# WikiTFT-2_8.net
KiCad netlist of a schematic drawn in Altium Designer
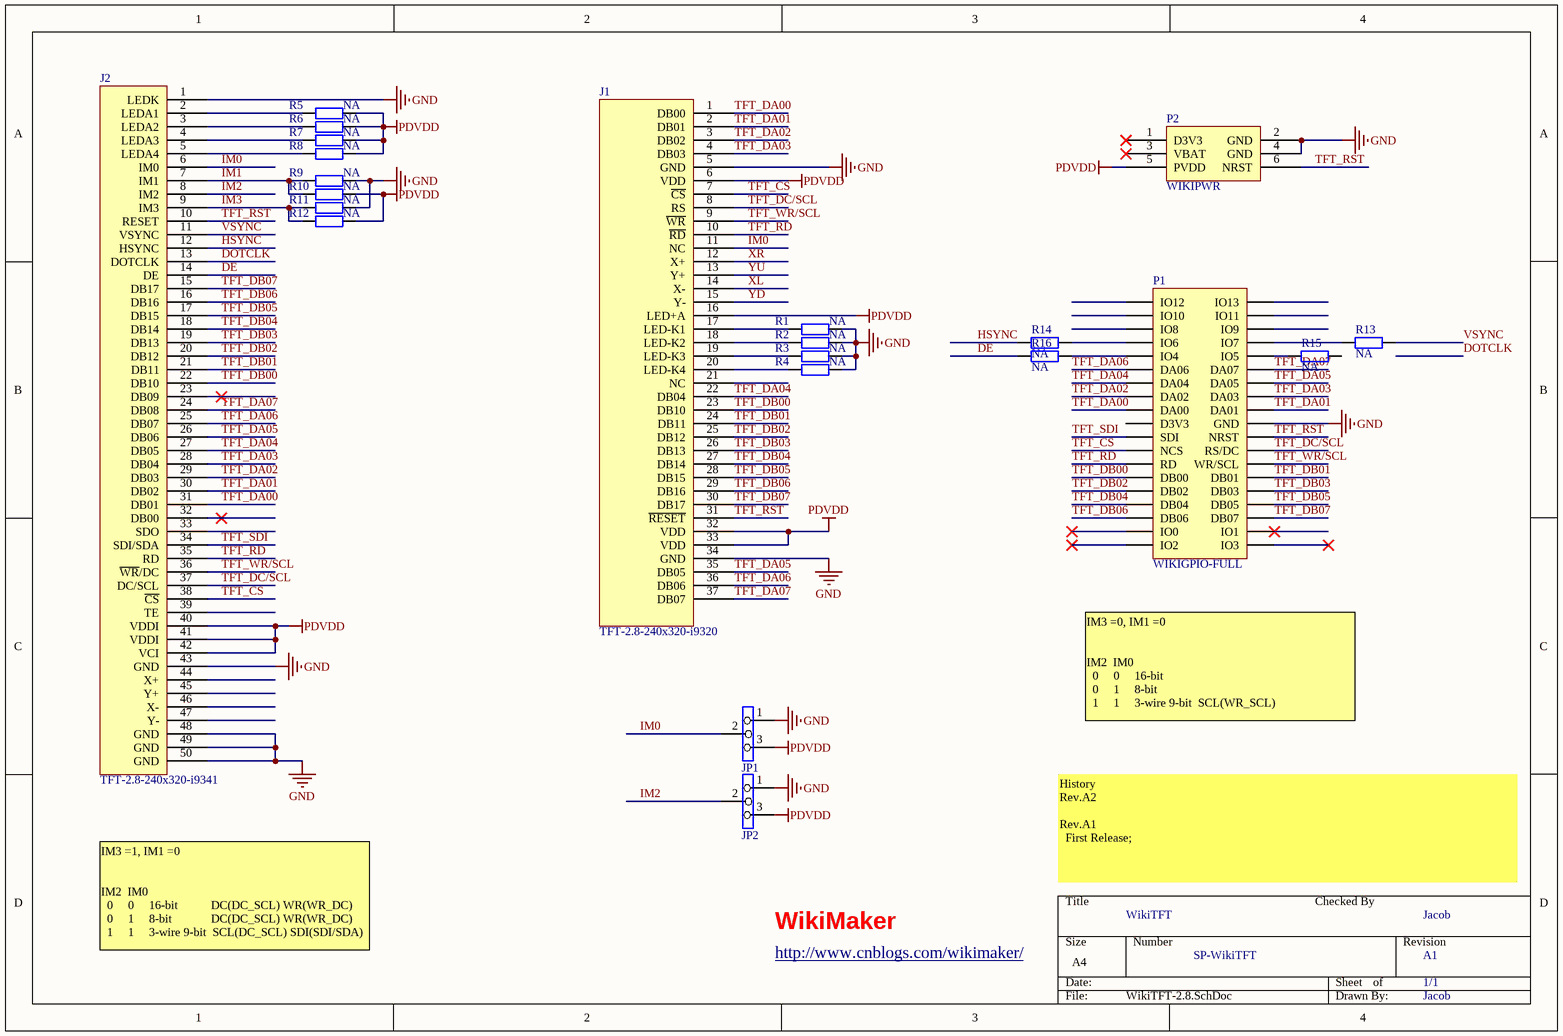
[diagram p0: WikiTFT-2.8.SchDoc]

(export (version "E")
  (design (tool "Eeschema 10.0.6"))
  (components
    (comp (ref "J1")
      (value "TFT-2.8-240x320-i9320")
      (footprint "TFT-PIN37-1.0MM")
      (description "i9320-240x320")
      (libsource (lib "Misc") (part "TFT-2.8-240x320-i9320"))
    )
    (comp (ref "J2")
      (value "TFT-2.8-240x320-i9341")
      (footprint "FPC-0.5-PIN50")
      (libsource (lib "Misc") (part "TFT-2.8-240x320-i9341-PIN50-FPC"))
    )
    (comp (ref "JP1") (value "Jumper3") (footprint "HDR1X3/2.00mm") (libsource (lib "Misc") (part "Jumper3")))
    (comp (ref "JP2") (value "Jumper3") (footprint "HDR1X3/2.00mm") (libsource (lib "Misc") (part "Jumper3")))
    (comp (ref "P1")
      (value "WIKIGPIO-FULL")
      (footprint "WIKIGPIO-FULL")
      (description "Header, 19-Pin, Dual row")
      (fields (field (name "PUBLISHER") "Altium Limited"))
      (libsource (lib "Connector") (part "WIKIGPIO-FULL"))
    )
    (comp (ref "P2")
      (value "WIKIPWR")
      (footprint "WIKIPWR")
      (description "PWR HDR")
      (libsource (lib "Connector") (part "WIKIPWR"))
    )
    (comp (ref "R1")
      (value "NA")
      (footprint "0603M")
      (description "Resistor")
      (fields (field (name "PUBLISHER") "Altium Limited"))
      (libsource (lib "CT107D_SUDA") (part "Res"))
    )
    (comp (ref "R2")
      (value "NA")
      (footprint "0603M")
      (description "Resistor")
      (fields (field (name "PUBLISHER") "Altium Limited"))
      (libsource (lib "CT107D_SUDA") (part "Res"))
    )
    (comp (ref "R3")
      (value "NA")
      (footprint "0603M")
      (description "Resistor")
      (fields (field (name "PUBLISHER") "Altium Limited"))
      (libsource (lib "CT107D_SUDA") (part "Res"))
    )
    (comp (ref "R4")
      (value "NA")
      (footprint "0603M")
      (description "Resistor")
      (fields (field (name "PUBLISHER") "Altium Limited"))
      (libsource (lib "CT107D_SUDA") (part "Res"))
    )
    (comp (ref "R5")
      (value "NA")
      (footprint "0603M")
      (description "Resistor")
      (fields (field (name "PUBLISHER") "Altium Limited"))
      (libsource (lib "") (part "Res_2"))
    )
    (comp (ref "R6")
      (value "NA")
      (footprint "0603M")
      (description "Resistor")
      (fields (field (name "PUBLISHER") "Altium Limited"))
      (libsource (lib "") (part "Res_2"))
    )
    (comp (ref "R7")
      (value "NA")
      (footprint "0603M")
      (description "Resistor")
      (fields (field (name "PUBLISHER") "Altium Limited"))
      (libsource (lib "") (part "Res_2"))
    )
    (comp (ref "R8")
      (value "NA")
      (footprint "0603M")
      (description "Resistor")
      (fields (field (name "PUBLISHER") "Altium Limited"))
      (libsource (lib "") (part "Res_2"))
    )
    (comp (ref "R9")
      (value "NA")
      (footprint "0603M")
      (description "Resistor")
      (fields (field (name "PUBLISHER") "Altium Limited"))
      (libsource (lib "") (part "Res_2"))
    )
    (comp (ref "R10")
      (value "NA")
      (footprint "0603M")
      (description "Resistor")
      (fields (field (name "PUBLISHER") "Altium Limited"))
      (libsource (lib "") (part "Res_2"))
    )
    (comp (ref "R11")
      (value "NA")
      (footprint "0603M")
      (description "Resistor")
      (fields (field (name "PUBLISHER") "Altium Limited"))
      (libsource (lib "") (part "Res_2"))
    )
    (comp (ref "R12")
      (value "NA")
      (footprint "0603M")
      (description "Resistor")
      (fields (field (name "PUBLISHER") "Altium Limited"))
      (libsource (lib "") (part "Res_2"))
    )
    (comp (ref "R13")
      (value "NA")
      (footprint "0603M")
      (description "Resistor")
      (fields (field (name "PUBLISHER") "Altium Limited"))
      (libsource (lib "") (part "Res_1"))
    )
    (comp (ref "R14")
      (value "NA")
      (footprint "0603M")
      (description "Resistor")
      (fields (field (name "PUBLISHER") "Altium Limited"))
      (libsource (lib "") (part "Res_1"))
    )
    (comp (ref "R15")
      (value "NA")
      (footprint "0603M")
      (description "Resistor")
      (fields (field (name "PUBLISHER") "Altium Limited"))
      (libsource (lib "") (part "Res_1"))
    )
    (comp (ref "R16")
      (value "NA")
      (footprint "0603M")
      (description "Resistor")
      (fields (field (name "PUBLISHER") "Altium Limited"))
      (libsource (lib "") (part "Res_1"))
    )
  )
  (nets
    (net (code "1") (name "/DE") (class "Default")
      (node (ref "J2") (pin "14") (pinfunction "DE_14") (pintype "passive"))
      (node (ref "R16") (pin "1") (pinfunction "1_1") (pintype "passive"))
    )
    (net (code "2") (name "/DOTCLK") (class "Default")
      (node (ref "J2") (pin "13") (pinfunction "DOTCLK_13") (pintype "passive"))
    )
    (net (code "3") (name "/HSYNC") (class "Default")
      (node (ref "J2") (pin "12") (pinfunction "HSYNC_12") (pintype "passive"))
      (node (ref "R14") (pin "1") (pinfunction "1_1") (pintype "passive"))
    )
    (net (code "4") (name "/IM0") (class "Default")
      (node (ref "J1") (pin "11") (pinfunction "NC_11") (pintype "passive"))
      (node (ref "J2") (pin "6") (pinfunction "IM0_6") (pintype "passive"))
      (node (ref "JP1") (pin "2") (pintype "passive"))
    )
    (net (code "5") (name "/IM1") (class "Default")
      (node (ref "J2") (pin "7") (pinfunction "IM1_7") (pintype "passive"))
      (node (ref "R10") (pin "2") (pinfunction "2_2") (pintype "passive"))
      (node (ref "R9") (pin "2") (pinfunction "2_2") (pintype "passive"))
    )
    (net (code "6") (name "/IM2") (class "Default")
      (node (ref "J2") (pin "8") (pinfunction "IM2_8") (pintype "passive"))
      (node (ref "JP2") (pin "2") (pintype "passive"))
    )
    (net (code "7") (name "/IM3") (class "Default")
      (node (ref "J2") (pin "9") (pinfunction "IM3_9") (pintype "passive"))
      (node (ref "R11") (pin "2") (pinfunction "2_2") (pintype "passive"))
      (node (ref "R12") (pin "2") (pinfunction "2_2") (pintype "passive"))
    )
    (net (code "8") (name "/TFT_CS") (class "Default")
      (node (ref "J1") (pin "7") (pinfunction "~{CS}_7") (pintype "passive"))
      (node (ref "J2") (pin "38") (pinfunction "~{CS}_38") (pintype "passive"))
      (node (ref "P1") (pin "23") (pinfunction "NCS_23") (pintype "passive"))
    )
    (net (code "9") (name "/TFT_DA00") (class "Default")
      (node (ref "J1") (pin "1") (pinfunction "DB00_1") (pintype "passive"))
      (node (ref "J2") (pin "31") (pinfunction "DB01_31") (pintype "passive"))
      (node (ref "P1") (pin "17") (pinfunction "DA00_17") (pintype "passive"))
    )
    (net (code "10") (name "/TFT_DA01") (class "Default")
      (node (ref "J1") (pin "2") (pinfunction "DB01_2") (pintype "passive"))
      (node (ref "J2") (pin "30") (pinfunction "DB02_30") (pintype "passive"))
      (node (ref "P1") (pin "18") (pinfunction "DA01_18") (pintype "passive"))
    )
    (net (code "11") (name "/TFT_DA02") (class "Default")
      (node (ref "J1") (pin "3") (pinfunction "DB02_3") (pintype "passive"))
      (node (ref "J2") (pin "29") (pinfunction "DB03_29") (pintype "passive"))
      (node (ref "P1") (pin "15") (pinfunction "DA02_15") (pintype "passive"))
    )
    (net (code "12") (name "/TFT_DA03") (class "Default")
      (node (ref "J1") (pin "4") (pinfunction "DB03_4") (pintype "passive"))
      (node (ref "J2") (pin "28") (pinfunction "DB04_28") (pintype "passive"))
      (node (ref "P1") (pin "16") (pinfunction "DA03_16") (pintype "passive"))
    )
    (net (code "13") (name "/TFT_DA04") (class "Default")
      (node (ref "J1") (pin "22") (pinfunction "DB04_22") (pintype "passive"))
      (node (ref "J2") (pin "27") (pinfunction "DB05_27") (pintype "passive"))
      (node (ref "P1") (pin "13") (pinfunction "DA04_13") (pintype "passive"))
    )
    (net (code "14") (name "/TFT_DA05") (class "Default")
      (node (ref "J1") (pin "35") (pinfunction "DB05_35") (pintype "passive"))
      (node (ref "J2") (pin "26") (pinfunction "DB06_26") (pintype "passive"))
      (node (ref "P1") (pin "14") (pinfunction "DA05_14") (pintype "passive"))
    )
    (net (code "15") (name "/TFT_DA06") (class "Default")
      (node (ref "J1") (pin "36") (pinfunction "DB06_36") (pintype "passive"))
      (node (ref "J2") (pin "25") (pinfunction "DB07_25") (pintype "passive"))
      (node (ref "P1") (pin "11") (pinfunction "DA06_11") (pintype "passive"))
    )
    (net (code "16") (name "/TFT_DA07") (class "Default")
      (node (ref "J1") (pin "37") (pinfunction "DB07_37") (pintype "passive"))
      (node (ref "J2") (pin "24") (pinfunction "DB08_24") (pintype "passive"))
      (node (ref "P1") (pin "12") (pinfunction "DA07_12") (pintype "passive"))
    )
    (net (code "17") (name "/TFT_DB00") (class "Default")
      (node (ref "J1") (pin "23") (pinfunction "DB10_23") (pintype "passive"))
      (node (ref "J2") (pin "22") (pinfunction "DB10_22") (pintype "passive"))
      (node (ref "P1") (pin "27") (pinfunction "DB00_27") (pintype "passive"))
    )
    (net (code "18") (name "/TFT_DB01") (class "Default")
      (node (ref "J1") (pin "24") (pinfunction "DB11_24") (pintype "passive"))
      (node (ref "J2") (pin "21") (pinfunction "DB11_21") (pintype "passive"))
      (node (ref "P1") (pin "28") (pinfunction "DB01_28") (pintype "passive"))
    )
    (net (code "19") (name "/TFT_DB02") (class "Default")
      (node (ref "J1") (pin "25") (pinfunction "DB12_25") (pintype "passive"))
      (node (ref "J2") (pin "20") (pinfunction "DB12_20") (pintype "passive"))
      (node (ref "P1") (pin "29") (pinfunction "DB02_29") (pintype "passive"))
    )
    (net (code "20") (name "/TFT_DB03") (class "Default")
      (node (ref "J1") (pin "26") (pinfunction "DB13_26") (pintype "passive"))
      (node (ref "J2") (pin "19") (pinfunction "DB13_19") (pintype "passive"))
      (node (ref "P1") (pin "30") (pinfunction "DB03_30") (pintype "passive"))
    )
    (net (code "21") (name "/TFT_DB04") (class "Default")
      (node (ref "J1") (pin "27") (pinfunction "DB14_27") (pintype "passive"))
      (node (ref "J2") (pin "18") (pinfunction "DB14_18") (pintype "passive"))
      (node (ref "P1") (pin "31") (pinfunction "DB04_31") (pintype "passive"))
    )
    (net (code "22") (name "/TFT_DB05") (class "Default")
      (node (ref "J1") (pin "28") (pinfunction "DB15_28") (pintype "passive"))
      (node (ref "J2") (pin "17") (pinfunction "DB15_17") (pintype "passive"))
      (node (ref "P1") (pin "32") (pinfunction "DB05_32") (pintype "passive"))
    )
    (net (code "23") (name "/TFT_DB06") (class "Default")
      (node (ref "J1") (pin "29") (pinfunction "DB16_29") (pintype "passive"))
      (node (ref "J2") (pin "16") (pinfunction "DB16_16") (pintype "passive"))
      (node (ref "P1") (pin "33") (pinfunction "DB06_33") (pintype "passive"))
    )
    (net (code "24") (name "/TFT_DB07") (class "Default")
      (node (ref "J1") (pin "30") (pinfunction "DB17_30") (pintype "passive"))
      (node (ref "J2") (pin "15") (pinfunction "DB17_15") (pintype "passive"))
      (node (ref "P1") (pin "34") (pinfunction "DB07_34") (pintype "passive"))
    )
    (net (code "25") (name "/TFT_DC{slash}SCL") (class "Default")
      (node (ref "J1") (pin "8") (pinfunction "RS_8") (pintype "passive"))
      (node (ref "J2") (pin "37") (pinfunction "DC/SCL_37") (pintype "passive"))
      (node (ref "P1") (pin "24") (pinfunction "RS/DC_24") (pintype "passive"))
    )
    (net (code "26") (name "/TFT_RD") (class "Default")
      (node (ref "J1") (pin "10") (pinfunction "~{RD}_10") (pintype "passive"))
      (node (ref "J2") (pin "35") (pinfunction "RD_35") (pintype "passive"))
      (node (ref "P1") (pin "25") (pinfunction "RD_25") (pintype "passive"))
    )
    (net (code "27") (name "/TFT_RST") (class "Default")
      (node (ref "J1") (pin "31") (pinfunction "~{RESET}_31") (pintype "passive"))
      (node (ref "J2") (pin "10") (pinfunction "RESET_10") (pintype "passive"))
      (node (ref "P1") (pin "22") (pinfunction "NRST_22") (pintype "passive"))
      (node (ref "P2") (pin "6") (pinfunction "NRST_6") (pintype "passive"))
    )
    (net (code "28") (name "/TFT_SDI") (class "Default")
      (node (ref "J2") (pin "34") (pinfunction "SDI/SDA_34") (pintype "passive"))
      (node (ref "P1") (pin "21") (pinfunction "SDI_21") (pintype "passive"))
    )
    (net (code "29") (name "/TFT_WR{slash}SCL") (class "Default")
      (node (ref "J1") (pin "9") (pinfunction "~{WR}_9") (pintype "passive"))
      (node (ref "J2") (pin "36") (pinfunction "~{WR}/DC_36") (pintype "passive"))
      (node (ref "P1") (pin "26") (pinfunction "WR/SCL_26") (pintype "passive"))
    )
    (net (code "30") (name "/VSYNC") (class "Default")
      (node (ref "J2") (pin "11") (pinfunction "VSYNC_11") (pintype "passive"))
      (node (ref "R13") (pin "2") (pinfunction "2_2") (pintype "passive"))
    )
    (net (code "31") (name "/XL") (class "Default")
      (node (ref "J1") (pin "14") (pinfunction "X-_14") (pintype "passive"))
    )
    (net (code "32") (name "/XR") (class "Default")
      (node (ref "J1") (pin "12") (pinfunction "X+_12") (pintype "passive"))
    )
    (net (code "33") (name "/YD") (class "Default")
      (node (ref "J1") (pin "15") (pinfunction "Y-_15") (pintype "passive"))
    )
    (net (code "34") (name "/YU") (class "Default")
      (node (ref "J1") (pin "13") (pinfunction "Y+_13") (pintype "passive"))
    )
    (net (code "35") (name "GND") (class "Default")
      (node (ref "J1") (pin "34") (pinfunction "GND_34") (pintype "passive"))
      (node (ref "J1") (pin "5") (pinfunction "GND_5") (pintype "passive"))
      (node (ref "J2") (pin "1") (pinfunction "LEDK_1") (pintype "passive"))
      (node (ref "J2") (pin "43") (pinfunction "GND_43") (pintype "passive"))
      (node (ref "J2") (pin "48") (pinfunction "GND_48") (pintype "passive"))
      (node (ref "J2") (pin "49") (pinfunction "GND_49") (pintype "passive"))
      (node (ref "J2") (pin "50") (pinfunction "GND_50") (pintype "passive"))
      (node (ref "JP1") (pin "1") (pintype "passive"))
      (node (ref "JP2") (pin "1") (pintype "passive"))
      (node (ref "P1") (pin "20") (pinfunction "GND_20") (pintype "passive"))
      (node (ref "P2") (pin "2") (pinfunction "GND_2") (pintype "passive"))
      (node (ref "P2") (pin "4") (pinfunction "GND_4") (pintype "passive"))
      (node (ref "R1") (pin "1") (pinfunction "1_1") (pintype "passive"))
      (node (ref "R11") (pin "1") (pinfunction "1_1") (pintype "passive"))
      (node (ref "R2") (pin "1") (pinfunction "1_1") (pintype "passive"))
      (node (ref "R3") (pin "1") (pinfunction "1_1") (pintype "passive"))
      (node (ref "R4") (pin "1") (pinfunction "1_1") (pintype "passive"))
      (node (ref "R9") (pin "1") (pinfunction "1_1") (pintype "passive"))
    )
    (net (code "36") (name "Net-(J1-LED-K1)") (class "Default")
      (node (ref "J1") (pin "17") (pinfunction "LED-K1_17") (pintype "passive"))
      (node (ref "R1") (pin "2") (pinfunction "2_2") (pintype "passive"))
    )
    (net (code "37") (name "Net-(J1-LED-K2)") (class "Default")
      (node (ref "J1") (pin "18") (pinfunction "LED-K2_18") (pintype "passive"))
      (node (ref "R2") (pin "2") (pinfunction "2_2") (pintype "passive"))
    )
    (net (code "38") (name "Net-(J1-LED-K3)") (class "Default")
      (node (ref "J1") (pin "19") (pinfunction "LED-K3_19") (pintype "passive"))
      (node (ref "R3") (pin "2") (pinfunction "2_2") (pintype "passive"))
    )
    (net (code "39") (name "Net-(J1-LED-K4)") (class "Default")
      (node (ref "J1") (pin "20") (pinfunction "LED-K4_20") (pintype "passive"))
      (node (ref "R4") (pin "2") (pinfunction "2_2") (pintype "passive"))
    )
    (net (code "40") (name "Net-(J2-LEDA1)") (class "Default")
      (node (ref "J2") (pin "2") (pinfunction "LEDA1_2") (pintype "passive"))
      (node (ref "R5") (pin "2") (pinfunction "2_2") (pintype "passive"))
    )
    (net (code "41") (name "Net-(J2-LEDA2)") (class "Default")
      (node (ref "J2") (pin "3") (pinfunction "LEDA2_3") (pintype "passive"))
      (node (ref "R6") (pin "2") (pinfunction "2_2") (pintype "passive"))
    )
    (net (code "42") (name "Net-(J2-LEDA3)") (class "Default")
      (node (ref "J2") (pin "4") (pinfunction "LEDA3_4") (pintype "passive"))
      (node (ref "R7") (pin "2") (pinfunction "2_2") (pintype "passive"))
    )
    (net (code "43") (name "Net-(J2-LEDA4)") (class "Default")
      (node (ref "J2") (pin "5") (pinfunction "LEDA4_5") (pintype "passive"))
      (node (ref "R8") (pin "2") (pinfunction "2_2") (pintype "passive"))
    )
    (net (code "44") (name "Net-(P1-IO4)") (class "Default")
      (node (ref "P1") (pin "9") (pinfunction "IO4_9") (pintype "passive"))
      (node (ref "R16") (pin "2") (pinfunction "2_2") (pintype "passive"))
    )
    (net (code "45") (name "Net-(P1-IO5)") (class "Default")
      (node (ref "P1") (pin "10") (pinfunction "IO5_10") (pintype "passive"))
      (node (ref "R15") (pin "1") (pinfunction "1_1") (pintype "passive"))
    )
    (net (code "46") (name "Net-(P1-IO6)") (class "Default")
      (node (ref "P1") (pin "7") (pinfunction "IO6_7") (pintype "passive"))
      (node (ref "R14") (pin "2") (pinfunction "2_2") (pintype "passive"))
    )
    (net (code "47") (name "Net-(P1-IO7)") (class "Default")
      (node (ref "P1") (pin "8") (pinfunction "IO7_8") (pintype "passive"))
      (node (ref "R13") (pin "1") (pinfunction "1_1") (pintype "passive"))
    )
    (net (code "48") (name "PDVDD") (class "Default")
      (node (ref "J1") (pin "16") (pinfunction "LED+A_16") (pintype "passive"))
      (node (ref "J1") (pin "32") (pinfunction "VDD_32") (pintype "passive"))
      (node (ref "J1") (pin "33") (pinfunction "VDD_33") (pintype "passive"))
      (node (ref "J1") (pin "6") (pinfunction "VDD_6") (pintype "passive"))
      (node (ref "J2") (pin "40") (pinfunction "VDDI_40") (pintype "passive"))
      (node (ref "J2") (pin "41") (pinfunction "VDDI_41") (pintype "passive"))
      (node (ref "J2") (pin "42") (pinfunction "VCI_42") (pintype "passive"))
      (node (ref "JP1") (pin "3") (pintype "passive"))
      (node (ref "JP2") (pin "3") (pintype "passive"))
      (node (ref "P2") (pin "5") (pinfunction "PVDD_5") (pintype "passive"))
      (node (ref "R10") (pin "1") (pinfunction "1_1") (pintype "passive"))
      (node (ref "R12") (pin "1") (pinfunction "1_1") (pintype "passive"))
      (node (ref "R5") (pin "1") (pinfunction "1_1") (pintype "passive"))
      (node (ref "R6") (pin "1") (pinfunction "1_1") (pintype "passive"))
      (node (ref "R7") (pin "1") (pinfunction "1_1") (pintype "passive"))
      (node (ref "R8") (pin "1") (pinfunction "1_1") (pintype "passive"))
    )
    (net (code "49") (name "unconnected-(J1-NC-Pad21)") (class "Default")
      (node (ref "J1") (pin "21") (pinfunction "NC_21") (pintype "passive"))
    )
    (net (code "50") (name "unconnected-(J2-DB00-Pad32)") (class "Default")
      (node (ref "J2") (pin "32") (pinfunction "DB00_32") (pintype "passive+no_connect"))
    )
    (net (code "51") (name "unconnected-(J2-DB09-Pad23)") (class "Default")
      (node (ref "J2") (pin "23") (pinfunction "DB09_23") (pintype "passive+no_connect"))
    )
    (net (code "52") (name "unconnected-(J2-SDO-Pad33)") (class "Default")
      (node (ref "J2") (pin "33") (pinfunction "SDO_33") (pintype "passive"))
    )
    (net (code "53") (name "unconnected-(J2-TE-Pad39)") (class "Default")
      (node (ref "J2") (pin "39") (pinfunction "TE_39") (pintype "passive"))
    )
    (net (code "54") (name "unconnected-(J2-X+-Pad44)") (class "Default")
      (node (ref "J2") (pin "44") (pinfunction "X+_44") (pintype "passive"))
    )
    (net (code "55") (name "unconnected-(J2-X--Pad46)") (class "Default")
      (node (ref "J2") (pin "46") (pinfunction "X-_46") (pintype "passive"))
    )
    (net (code "56") (name "unconnected-(J2-Y+-Pad45)") (class "Default")
      (node (ref "J2") (pin "45") (pinfunction "Y+_45") (pintype "passive"))
    )
    (net (code "57") (name "unconnected-(J2-Y--Pad47)") (class "Default")
      (node (ref "J2") (pin "47") (pinfunction "Y-_47") (pintype "passive"))
    )
    (net (code "58") (name "unconnected-(P1-D3V3-Pad19)") (class "Default")
      (node (ref "P1") (pin "19") (pinfunction "D3V3_19") (pintype "passive"))
    )
    (net (code "59") (name "unconnected-(P1-IO0-Pad35)") (class "Default")
      (node (ref "P1") (pin "35") (pinfunction "IO0_35") (pintype "passive+no_connect"))
    )
    (net (code "60") (name "unconnected-(P1-IO1-Pad36)") (class "Default")
      (node (ref "P1") (pin "36") (pinfunction "IO1_36") (pintype "passive+no_connect"))
    )
    (net (code "61") (name "unconnected-(P1-IO2-Pad37)") (class "Default")
      (node (ref "P1") (pin "37") (pinfunction "IO2_37") (pintype "passive+no_connect"))
    )
    (net (code "62") (name "unconnected-(P1-IO3-Pad38)") (class "Default")
      (node (ref "P1") (pin "38") (pinfunction "IO3_38") (pintype "passive+no_connect"))
    )
    (net (code "63") (name "unconnected-(P1-IO8-Pad5)") (class "Default")
      (node (ref "P1") (pin "5") (pinfunction "IO8_5") (pintype "passive"))
    )
    (net (code "64") (name "unconnected-(P1-IO9-Pad6)") (class "Default")
      (node (ref "P1") (pin "6") (pinfunction "IO9_6") (pintype "passive"))
    )
    (net (code "65") (name "unconnected-(P1-IO10-Pad3)") (class "Default")
      (node (ref "P1") (pin "3") (pinfunction "IO10_3") (pintype "passive"))
    )
    (net (code "66") (name "unconnected-(P1-IO11-Pad4)") (class "Default")
      (node (ref "P1") (pin "4") (pinfunction "IO11_4") (pintype "passive"))
    )
    (net (code "67") (name "unconnected-(P1-IO12-Pad1)") (class "Default")
      (node (ref "P1") (pin "1") (pinfunction "IO12_1") (pintype "passive"))
    )
    (net (code "68") (name "unconnected-(P1-IO13-Pad2)") (class "Default")
      (node (ref "P1") (pin "2") (pinfunction "IO13_2") (pintype "passive"))
    )
    (net (code "69") (name "unconnected-(P2-D3V3-Pad1)") (class "Default")
      (node (ref "P2") (pin "1") (pinfunction "D3V3_1") (pintype "passive+no_connect"))
    )
    (net (code "70") (name "unconnected-(P2-VBAT-Pad3)") (class "Default")
      (node (ref "P2") (pin "3") (pinfunction "VBAT_3") (pintype "passive+no_connect"))
    )
    (net (code "71") (name "unconnected-(R15-Pad2)") (class "Default")
      (node (ref "R15") (pin "2") (pinfunction "2_2") (pintype "passive"))
    )
  )
)
